# gadgiteration_v21.net
KiCad netlist of a schematic drawn in EAGLE
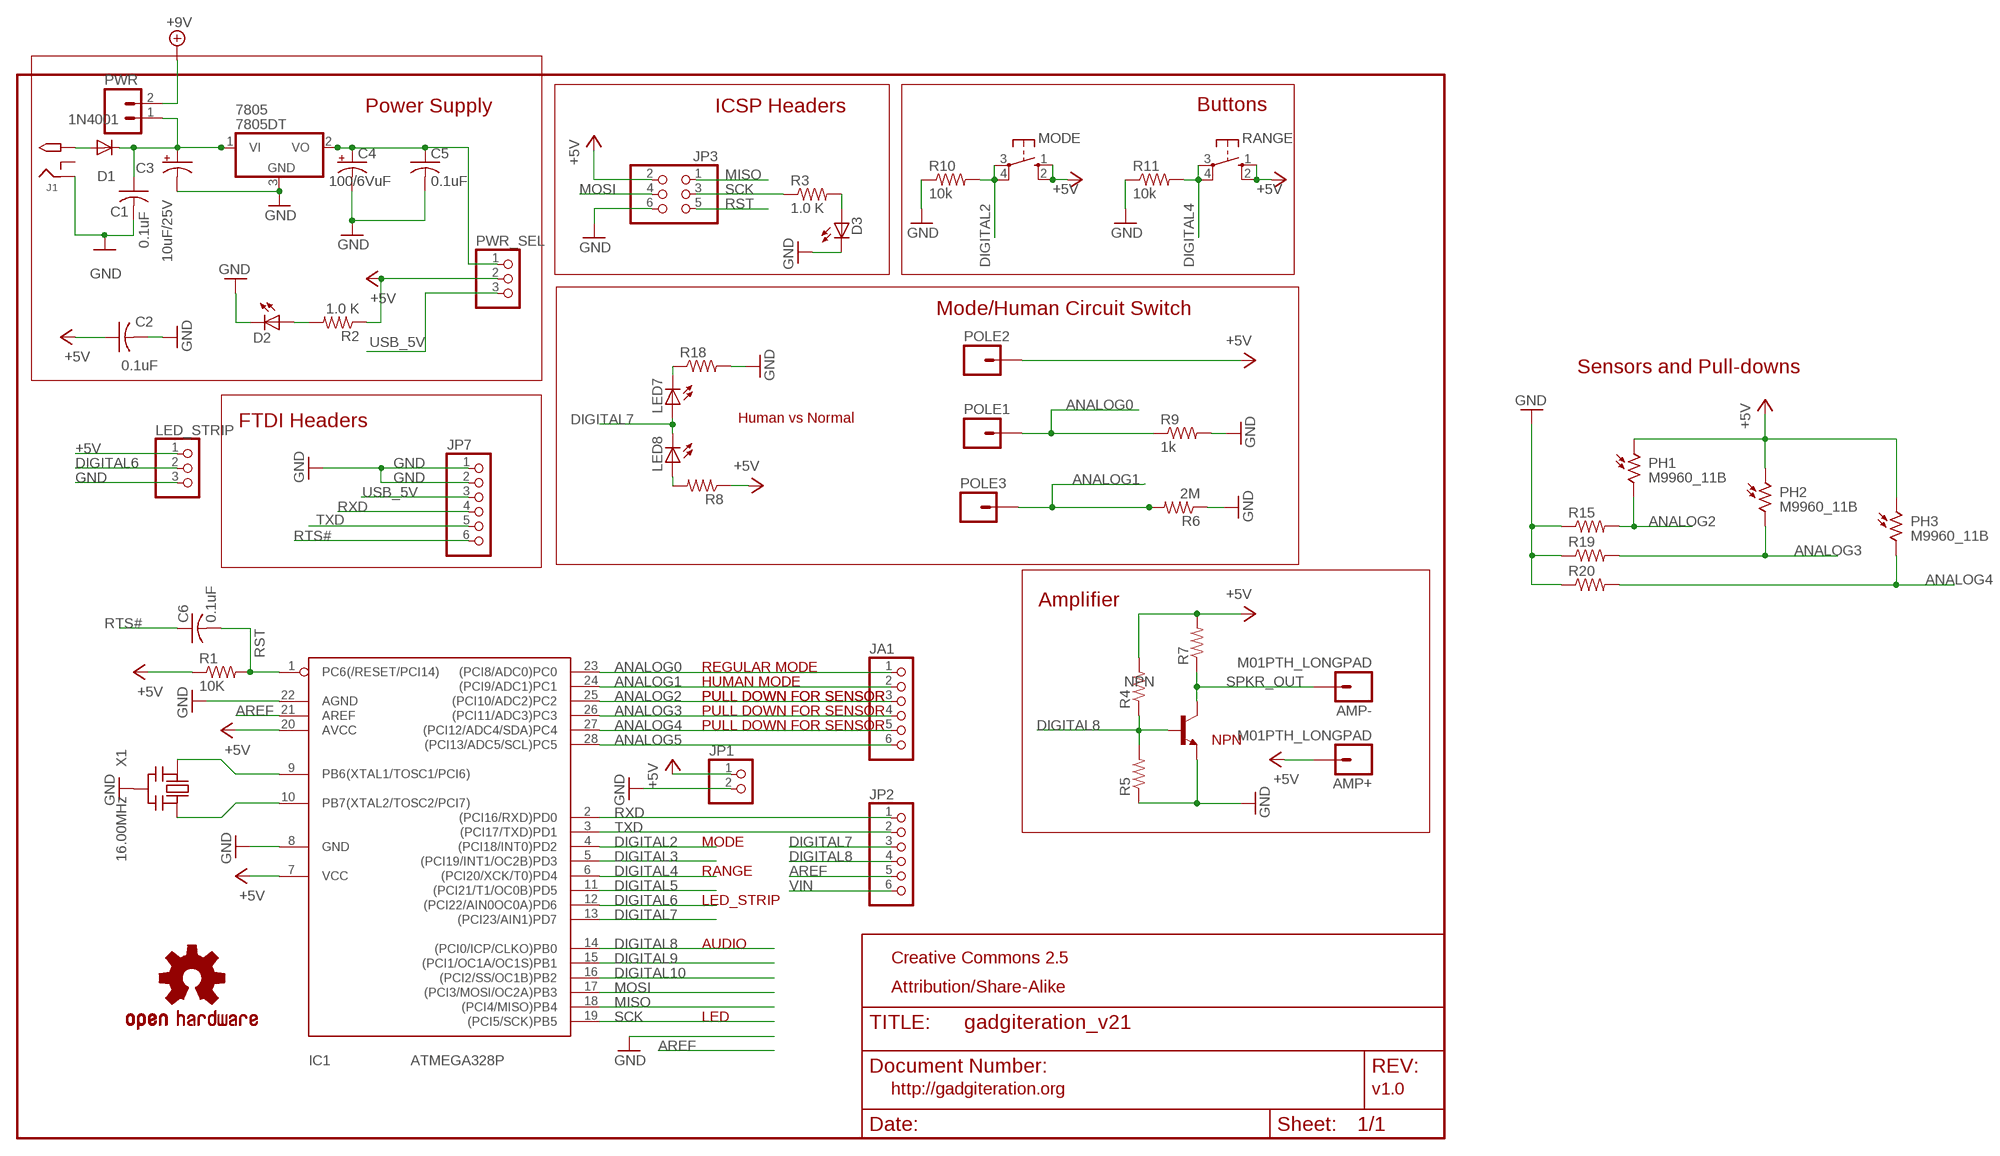
[diagram p0: schematic, sheet 1]

(export (version "E")
  (design (tool "Eeschema 10.0.6"))
  (components
    (comp (ref "7805")
      (value "7805DT")
      (footprint "eagle-import:TO252")
      (libsource (lib "eagle-import") (part "78DT05"))
    )
    (comp (ref "AMP+")
      (value "M01PTH_LONGPAD")
      (footprint "eagle-import:1X01_LONGPAD")
      (libsource (lib "eagle-import") (part "M01PTH_LONGPAD"))
    )
    (comp (ref "AMP-")
      (value "M01PTH_LONGPAD")
      (footprint "eagle-import:1X01_LONGPAD")
      (libsource (lib "eagle-import") (part "M01PTH_LONGPAD"))
    )
    (comp (ref "C1")
      (value "0.1uF")
      (footprint "eagle-import:C025-025X050")
      (libsource (lib "eagle-import") (part "C-US025-025X050"))
    )
    (comp (ref "C2")
      (value "0.1uF")
      (footprint "eagle-import:C025-025X050")
      (libsource (lib "eagle-import") (part "C-US025-025X050"))
    )
    (comp (ref "C3")
      (value "10uF/25V")
      (footprint "eagle-import:E2,5-6")
      (libsource (lib "eagle-import") (part "CPOL-USE2.5-6"))
    )
    (comp (ref "C4")
      (value "100/6VuF")
      (footprint "eagle-import:E2,5-6")
      (libsource (lib "eagle-import") (part "CPOL-USE2.5-6"))
    )
    (comp (ref "C5")
      (value "0.1uF")
      (footprint "eagle-import:C025-025X050")
      (libsource (lib "eagle-import") (part "C-US025-025X050"))
    )
    (comp (ref "C6")
      (value "0.1uF")
      (footprint "eagle-import:C025-025X050")
      (libsource (lib "eagle-import") (part "C-US025-025X050"))
    )
    (comp (ref "D1")
      (value "1N4001")
      (footprint "eagle-import:DIODE-1N4001")
      (libsource (lib "eagle-import") (part "DIODEPTH"))
    )
    (comp (ref "D2")
      (value "LED3MM")
      (footprint "eagle-import:LED3MM")
      (libsource (lib "eagle-import") (part "minimidi_LED3MM"))
    )
    (comp (ref "D3")
      (value "Green")
      (footprint "eagle-import:LED3MM")
      (libsource (lib "eagle-import") (part "minimidi_LED3MM"))
    )
    (comp (ref "IC1")
      (value "ATMEGA328P")
      (footprint "eagle-import:DIL28_3")
      (libsource (lib "eagle-import") (part "ATMEGA168PROUND"))
    )
    (comp (ref "J1")
      (value "2.1MMJACK")
      (footprint "eagle-import:PJ-102A")
      (libsource (lib "eagle-import") (part "2.1MMJACK"))
    )
    (comp (ref "JA1")
      (value "PINHD-1X6CB")
      (footprint "eagle-import:1X06-CLEANBIG")
      (libsource (lib "eagle-import") (part "carduino_PINHD-1X6CB"))
    )
    (comp (ref "JP1")
      (value "PINHD-1X2CB")
      (footprint "eagle-import:1X02-CB")
      (libsource (lib "eagle-import") (part "PINHD-1X2CB"))
    )
    (comp (ref "JP2")
      (value "PINHD-1X6CB")
      (footprint "eagle-import:1X06-CLEANBIG")
      (libsource (lib "eagle-import") (part "PINHD-1X6CB"))
    )
    (comp (ref "JP3")
      (value "PINHD-2X3")
      (footprint "eagle-import:2X03")
      (libsource (lib "eagle-import") (part "PINHD-2X3"))
    )
    (comp (ref "JP7")
      (value "PINHD-1X6CLEAN")
      (footprint "eagle-import:1X06-CLEAN")
      (libsource (lib "eagle-import") (part "carduino_PINHD-1X6CLEAN"))
    )
    (comp (ref "LED7")
      (value "LED3MM")
      (footprint "eagle-import:LED3MM")
      (libsource (lib "eagle-import") (part "LED3MM"))
    )
    (comp (ref "LED8")
      (value "LED3MM")
      (footprint "eagle-import:LED3MM")
      (libsource (lib "eagle-import") (part "LED3MM"))
    )
    (comp (ref "LED_STRIP")
      (value "PINHD-1X3")
      (footprint "eagle-import:1X03")
      (libsource (lib "eagle-import") (part "PINHD-1X3"))
    )
    (comp (ref "LOGO1")
      (value "OSHW-LOGOM")
      (footprint "eagle-import:OSHW-LOGO-M")
      (libsource (lib "eagle-import") (part "OSHW-LOGOM"))
    )
    (comp (ref "MODE")
      (value "10-XX")
      (footprint "eagle-import:B3F-10XX")
      (libsource (lib "eagle-import") (part "10-XX"))
    )
    (comp (ref "NPN")
      (value "-NPN-TO220V")
      (footprint "eagle-import:TO220V")
      (libsource (lib "eagle-import") (part "-NPN-TO220V"))
    )
    (comp (ref "PH1")
      (value "M9960_11B")
      (footprint "eagle-import:M9960")
      (libsource (lib "eagle-import") (part "M9960_11B"))
    )
    (comp (ref "PH2")
      (value "M9960_11B")
      (footprint "eagle-import:M9960")
      (libsource (lib "eagle-import") (part "M9960_11B"))
    )
    (comp (ref "PH3")
      (value "M9960_11B")
      (footprint "eagle-import:M9960")
      (libsource (lib "eagle-import") (part "M9960_11B"))
    )
    (comp (ref "POLE1")
      (value "M01PTH_LONGPAD")
      (footprint "eagle-import:1X01_LONGPAD")
      (libsource (lib "eagle-import") (part "M01PTH_LONGPAD"))
    )
    (comp (ref "POLE2")
      (value "M01PTH_LONGPAD")
      (footprint "eagle-import:1X01_LONGPAD")
      (libsource (lib "eagle-import") (part "M01PTH_LONGPAD"))
    )
    (comp (ref "POLE3")
      (value "M01PTH_LONGPAD")
      (footprint "eagle-import:1X01_LONGPAD")
      (libsource (lib "eagle-import") (part "M01PTH_LONGPAD"))
    )
    (comp (ref "PWR")
      (value "M02LOCK")
      (footprint "eagle-import:1X02_LOCK")
      (libsource (lib "eagle-import") (part "M02LOCK"))
    )
    (comp (ref "PWR_SEL")
      (value "PINHD-1X3")
      (footprint "eagle-import:1X03")
      (libsource (lib "eagle-import") (part "PINHD-1X3"))
    )
    (comp (ref "R1")
      (value "10K")
      (footprint "eagle-import:0204_5")
      (libsource (lib "eagle-import") (part "R-US_0204/5"))
    )
    (comp (ref "R2")
      (value "1.0 K")
      (footprint "eagle-import:0204_5")
      (libsource (lib "eagle-import") (part "R-US_0204/5"))
    )
    (comp (ref "R3")
      (value "1.0 K")
      (footprint "eagle-import:0204_5")
      (libsource (lib "eagle-import") (part "R-US_0204/5"))
    )
    (comp (ref "R4")
      (value "R-US_0204/5")
      (footprint "eagle-import:0204_5")
      (libsource (lib "eagle-import") (part "R-US_0204/5"))
    )
    (comp (ref "R5")
      (value "R-US_0204/5")
      (footprint "eagle-import:0204_5")
      (libsource (lib "eagle-import") (part "R-US_0204/5"))
    )
    (comp (ref "R6")
      (value "2M")
      (footprint "eagle-import:0204_5")
      (libsource (lib "eagle-import") (part "R-US_0204/5"))
    )
    (comp (ref "R7")
      (value "R-US_0204/5")
      (footprint "eagle-import:0204_5")
      (libsource (lib "eagle-import") (part "R-US_0204/5"))
    )
    (comp (ref "R8")
      (value "R-US_0204/5")
      (footprint "eagle-import:0204_5")
      (libsource (lib "eagle-import") (part "R-US_0204/5"))
    )
    (comp (ref "R9")
      (value "1k")
      (footprint "eagle-import:0204_5")
      (libsource (lib "eagle-import") (part "R-US_0204/5"))
    )
    (comp (ref "R10")
      (value "10k")
      (footprint "eagle-import:0204_5")
      (libsource (lib "eagle-import") (part "R-US_0204/5"))
    )
    (comp (ref "R11")
      (value "10k")
      (footprint "eagle-import:0204_5")
      (libsource (lib "eagle-import") (part "R-US_0204/5"))
    )
    (comp (ref "R15")
      (value "R-US_0204/5")
      (footprint "eagle-import:0204_5")
      (libsource (lib "eagle-import") (part "R-US_0204/5"))
    )
    (comp (ref "R18")
      (value "R-US_0204/5")
      (footprint "eagle-import:0204_5")
      (libsource (lib "eagle-import") (part "R-US_0204/5"))
    )
    (comp (ref "R19")
      (value "R-US_0204/5")
      (footprint "eagle-import:0204_5")
      (libsource (lib "eagle-import") (part "R-US_0204/5"))
    )
    (comp (ref "R20")
      (value "R-US_0204/5")
      (footprint "eagle-import:0204_5")
      (libsource (lib "eagle-import") (part "R-US_0204/5"))
    )
    (comp (ref "RANGE")
      (value "10-XX")
      (footprint "eagle-import:B3F-10XX")
      (libsource (lib "eagle-import") (part "10-XX"))
    )
    (comp (ref "X1")
      (value "16.00MHz")
      (footprint "eagle-import:CERM_OSC")
      (libsource (lib "eagle-import") (part "CERMOSCILL"))
    )
  )
  (nets
    (net (code "1") (name "+5V") (class "Default")
      (node (ref "AMP+") (pin "1") (pinfunction "1_1") (pintype "passive"))
      (node (ref "C2") (pin "1") (pinfunction "1_1") (pintype "passive"))
      (node (ref "IC1") (pin "20") (pinfunction "AVCC_20") (pintype "bidirectional"))
      (node (ref "IC1") (pin "7") (pinfunction "VCC_7") (pintype "bidirectional"))
      (node (ref "JP1") (pin "1") (pinfunction "1_1") (pintype "passive"))
      (node (ref "JP3") (pin "2") (pinfunction "2_2") (pintype "passive"))
      (node (ref "LED_STRIP") (pin "1") (pinfunction "1_1") (pintype "passive"))
      (node (ref "MODE") (pin "1") (pinfunction "S_1") (pintype "passive"))
      (node (ref "MODE") (pin "2") (pinfunction "S1_2") (pintype "passive"))
      (node (ref "PH1") (pin "1") (pinfunction "1_1") (pintype "passive"))
      (node (ref "PH2") (pin "1") (pinfunction "1_1") (pintype "passive"))
      (node (ref "PH3") (pin "1") (pinfunction "1_1") (pintype "passive"))
      (node (ref "POLE2") (pin "1") (pinfunction "1_1") (pintype "passive"))
      (node (ref "PWR_SEL") (pin "2") (pinfunction "2_2") (pintype "passive"))
      (node (ref "R1") (pin "1") (pinfunction "1_1") (pintype "passive"))
      (node (ref "R2") (pin "1") (pinfunction "1_1") (pintype "passive"))
      (node (ref "R4") (pin "2") (pinfunction "2_2") (pintype "passive"))
      (node (ref "R7") (pin "2") (pinfunction "2_2") (pintype "passive"))
      (node (ref "R8") (pin "1") (pinfunction "1_1") (pintype "passive"))
      (node (ref "RANGE") (pin "1") (pinfunction "S_1") (pintype "passive"))
      (node (ref "RANGE") (pin "2") (pinfunction "S1_2") (pintype "passive"))
    )
    (net (code "2") (name "+9V") (class "Default")
      (node (ref "PWR") (pin "2") (pinfunction "2_2") (pintype "passive"))
    )
    (net (code "3") (name "/ANALOG0") (class "Default")
      (node (ref "IC1") (pin "23") (pinfunction "(PCI8/ADC0)PC0_23") (pintype "bidirectional"))
      (node (ref "JA1") (pin "1") (pinfunction "1_1") (pintype "passive"))
      (node (ref "POLE1") (pin "1") (pinfunction "1_1") (pintype "passive"))
      (node (ref "R9") (pin "1") (pinfunction "1_1") (pintype "passive"))
    )
    (net (code "4") (name "/ANALOG1") (class "Default")
      (node (ref "IC1") (pin "24") (pinfunction "(PCI9/ADC1)PC1_24") (pintype "bidirectional"))
      (node (ref "JA1") (pin "2") (pinfunction "2_2") (pintype "passive"))
      (node (ref "POLE3") (pin "1") (pinfunction "1_1") (pintype "passive"))
      (node (ref "R6") (pin "2") (pinfunction "2_2") (pintype "passive"))
    )
    (net (code "5") (name "/ANALOG2") (class "Default")
      (node (ref "IC1") (pin "25") (pinfunction "(PCI10/ADC2)PC2_25") (pintype "bidirectional"))
      (node (ref "JA1") (pin "3") (pinfunction "3_3") (pintype "passive"))
      (node (ref "PH1") (pin "2") (pinfunction "2_2") (pintype "passive"))
      (node (ref "R15") (pin "2") (pinfunction "2_2") (pintype "passive"))
    )
    (net (code "6") (name "/ANALOG3") (class "Default")
      (node (ref "IC1") (pin "26") (pinfunction "(PCI11/ADC3)PC3_26") (pintype "bidirectional"))
      (node (ref "JA1") (pin "4") (pinfunction "4_4") (pintype "passive"))
      (node (ref "PH2") (pin "2") (pinfunction "2_2") (pintype "passive"))
      (node (ref "R19") (pin "2") (pinfunction "2_2") (pintype "passive"))
    )
    (net (code "7") (name "/ANALOG4") (class "Default")
      (node (ref "IC1") (pin "27") (pinfunction "(PCI12/ADC4/SDA)PC4_27") (pintype "bidirectional"))
      (node (ref "JA1") (pin "5") (pinfunction "5_5") (pintype "passive"))
      (node (ref "PH3") (pin "2") (pinfunction "2_2") (pintype "passive"))
      (node (ref "R20") (pin "2") (pinfunction "2_2") (pintype "passive"))
    )
    (net (code "8") (name "/ANALOG5") (class "Default")
      (node (ref "IC1") (pin "28") (pinfunction "(PCI13/ADC5/SCL)PC5_28") (pintype "bidirectional"))
      (node (ref "JA1") (pin "6") (pinfunction "6_6") (pintype "passive"))
    )
    (net (code "9") (name "/AREF") (class "Default")
      (node (ref "IC1") (pin "21") (pinfunction "AREF_21") (pintype "bidirectional"))
      (node (ref "JP2") (pin "5") (pinfunction "5_5") (pintype "passive"))
    )
    (net (code "10") (name "/DIGITAL2") (class "Default")
      (node (ref "IC1") (pin "4") (pinfunction "(PCI18/INT0)PD2_4") (pintype "bidirectional"))
      (node (ref "MODE") (pin "3") (pinfunction "P_3") (pintype "passive"))
      (node (ref "MODE") (pin "4") (pinfunction "P1_4") (pintype "passive"))
      (node (ref "R10") (pin "2") (pinfunction "2_2") (pintype "passive"))
    )
    (net (code "11") (name "/DIGITAL3") (class "Default")
      (node (ref "IC1") (pin "5") (pinfunction "(PCI19/INT1/OC2B)PD3_5") (pintype "bidirectional"))
    )
    (net (code "12") (name "/DIGITAL4") (class "Default")
      (node (ref "IC1") (pin "6") (pinfunction "(PCI20/XCK/T0)PD4_6") (pintype "bidirectional"))
      (node (ref "R11") (pin "2") (pinfunction "2_2") (pintype "passive"))
      (node (ref "RANGE") (pin "3") (pinfunction "P_3") (pintype "passive"))
      (node (ref "RANGE") (pin "4") (pinfunction "P1_4") (pintype "passive"))
    )
    (net (code "13") (name "/DIGITAL5") (class "Default")
      (node (ref "IC1") (pin "11") (pinfunction "(PCI21/T1/OC0B)PD5_11") (pintype "bidirectional"))
    )
    (net (code "14") (name "/DIGITAL6") (class "Default")
      (node (ref "IC1") (pin "12") (pinfunction "(PCI22/AIN0OC0A)PD6_12") (pintype "bidirectional"))
      (node (ref "LED_STRIP") (pin "2") (pinfunction "2_2") (pintype "passive"))
    )
    (net (code "15") (name "/DIGITAL7") (class "Default")
      (node (ref "IC1") (pin "13") (pinfunction "(PCI23/AIN1)PD7_13") (pintype "bidirectional"))
      (node (ref "JP2") (pin "3") (pinfunction "3_3") (pintype "passive"))
      (node (ref "LED7") (pin "A") (pinfunction "A_A") (pintype "passive"))
      (node (ref "LED8") (pin "K") (pinfunction "C_K") (pintype "passive"))
    )
    (net (code "16") (name "/DIGITAL8") (class "Default")
      (node (ref "IC1") (pin "14") (pinfunction "(PCI0/ICP/CLKO)PB0_14") (pintype "bidirectional"))
      (node (ref "JP2") (pin "4") (pinfunction "4_4") (pintype "passive"))
      (node (ref "NPN") (pin "1") (pinfunction "B_1") (pintype "passive"))
      (node (ref "R4") (pin "1") (pinfunction "1_1") (pintype "passive"))
      (node (ref "R5") (pin "2") (pinfunction "2_2") (pintype "passive"))
    )
    (net (code "17") (name "/DIGITAL9") (class "Default")
      (node (ref "IC1") (pin "15") (pinfunction "(PCI1/OC1A/OC1S)PB1_15") (pintype "bidirectional"))
    )
    (net (code "18") (name "/DIGITAL10") (class "Default")
      (node (ref "IC1") (pin "16") (pinfunction "(PCI2/SS/OC1B)PB2_16") (pintype "bidirectional"))
    )
    (net (code "19") (name "/MISO") (class "Default")
      (node (ref "IC1") (pin "18") (pinfunction "(PCI4/MISO)PB4_18") (pintype "bidirectional"))
      (node (ref "JP3") (pin "1") (pinfunction "1_1") (pintype "passive"))
    )
    (net (code "20") (name "/MOSI") (class "Default")
      (node (ref "IC1") (pin "17") (pinfunction "(PCI3/MOSI/OC2A)PB3_17") (pintype "bidirectional"))
      (node (ref "JP3") (pin "4") (pinfunction "4_4") (pintype "passive"))
    )
    (net (code "21") (name "/RST") (class "Default")
      (node (ref "C6") (pin "2") (pinfunction "2_2") (pintype "passive"))
      (node (ref "IC1") (pin "1") (pinfunction "PC6(/RESET/PCI14)_1") (pintype "bidirectional"))
      (node (ref "JP3") (pin "5") (pinfunction "5_5") (pintype "passive"))
      (node (ref "R1") (pin "2") (pinfunction "2_2") (pintype "passive"))
    )
    (net (code "22") (name "/RTS#") (class "Default")
      (node (ref "C6") (pin "1") (pinfunction "1_1") (pintype "passive"))
      (node (ref "JP7") (pin "6") (pinfunction "6_6") (pintype "passive"))
    )
    (net (code "23") (name "/RXD") (class "Default")
      (node (ref "IC1") (pin "2") (pinfunction "(PCI16/RXD)PD0_2") (pintype "bidirectional"))
      (node (ref "JP2") (pin "1") (pinfunction "1_1") (pintype "passive"))
      (node (ref "JP7") (pin "4") (pinfunction "4_4") (pintype "passive"))
    )
    (net (code "24") (name "/SCK") (class "Default")
      (node (ref "IC1") (pin "19") (pinfunction "(PCI5/SCK)PB5_19") (pintype "bidirectional"))
      (node (ref "JP3") (pin "3") (pinfunction "3_3") (pintype "passive"))
      (node (ref "R3") (pin "1") (pinfunction "1_1") (pintype "passive"))
    )
    (net (code "25") (name "/SPKR_OUT") (class "Default")
      (node (ref "AMP-") (pin "1") (pinfunction "1_1") (pintype "passive"))
      (node (ref "NPN") (pin "2") (pinfunction "C_2") (pintype "passive"))
      (node (ref "R7") (pin "1") (pinfunction "1_1") (pintype "passive"))
    )
    (net (code "26") (name "/TXD") (class "Default")
      (node (ref "IC1") (pin "3") (pinfunction "(PCI17/TXD)PD1_3") (pintype "bidirectional"))
      (node (ref "JP2") (pin "2") (pinfunction "2_2") (pintype "passive"))
      (node (ref "JP7") (pin "5") (pinfunction "5_5") (pintype "passive"))
    )
    (net (code "27") (name "/USB_5V") (class "Default")
      (node (ref "JP7") (pin "3") (pinfunction "3_3") (pintype "passive"))
      (node (ref "PWR_SEL") (pin "3") (pinfunction "3_3") (pintype "passive"))
    )
    (net (code "28") (name "/VIN") (class "Default")
      (node (ref "7805") (pin "1") (pinfunction "VI_1") (pintype "input"))
      (node (ref "C1") (pin "1") (pinfunction "1_1") (pintype "passive"))
      (node (ref "C3") (pin "+") (pinfunction "+_+") (pintype "passive"))
      (node (ref "D1") (pin "C") (pinfunction "C_C") (pintype "passive"))
      (node (ref "JP2") (pin "6") (pinfunction "6_6") (pintype "passive"))
      (node (ref "PWR") (pin "1") (pinfunction "1_1") (pintype "passive"))
    )
    (net (code "29") (name "GND") (class "Default")
      (node (ref "7805") (pin "3") (pinfunction "GND_3") (pintype "passive"))
      (node (ref "C1") (pin "2") (pinfunction "2_2") (pintype "passive"))
      (node (ref "C2") (pin "2") (pinfunction "2_2") (pintype "passive"))
      (node (ref "C3") (pin "-") (pinfunction "-_-") (pintype "passive"))
      (node (ref "C4") (pin "-") (pinfunction "-_-") (pintype "passive"))
      (node (ref "C5") (pin "2") (pinfunction "2_2") (pintype "passive"))
      (node (ref "D2") (pin "K") (pinfunction "C_K") (pintype "passive"))
      (node (ref "D3") (pin "K") (pinfunction "C_K") (pintype "passive"))
      (node (ref "IC1") (pin "22") (pinfunction "AGND_22") (pintype "bidirectional"))
      (node (ref "IC1") (pin "8") (pinfunction "GND_8") (pintype "bidirectional"))
      (node (ref "J1") (pin "RING") (pinfunction "RING_RING") (pintype "bidirectional"))
      (node (ref "JP1") (pin "2") (pinfunction "2_2") (pintype "passive"))
      (node (ref "JP3") (pin "6") (pinfunction "6_6") (pintype "passive"))
      (node (ref "JP7") (pin "1") (pinfunction "1_1") (pintype "passive"))
      (node (ref "JP7") (pin "2") (pinfunction "2_2") (pintype "passive"))
      (node (ref "LED_STRIP") (pin "3") (pinfunction "3_3") (pintype "passive"))
      (node (ref "NPN") (pin "3") (pinfunction "E_3") (pintype "passive"))
      (node (ref "R10") (pin "1") (pinfunction "1_1") (pintype "passive"))
      (node (ref "R11") (pin "1") (pinfunction "1_1") (pintype "passive"))
      (node (ref "R15") (pin "1") (pinfunction "1_1") (pintype "passive"))
      (node (ref "R18") (pin "2") (pinfunction "2_2") (pintype "passive"))
      (node (ref "R19") (pin "1") (pinfunction "1_1") (pintype "passive"))
      (node (ref "R20") (pin "1") (pinfunction "1_1") (pintype "passive"))
      (node (ref "R5") (pin "1") (pinfunction "1_1") (pintype "passive"))
      (node (ref "R6") (pin "1") (pinfunction "1_1") (pintype "passive"))
      (node (ref "R9") (pin "2") (pinfunction "2_2") (pintype "passive"))
      (node (ref "X1") (pin "P$2") (pinfunction "GND_P$2") (pintype "bidirectional"))
    )
    (net (code "30") (name "Net-(7805-VO)") (class "Default")
      (node (ref "7805") (pin "2") (pinfunction "VO_2") (pintype "passive"))
      (node (ref "C4") (pin "+") (pinfunction "+_+") (pintype "passive"))
      (node (ref "C5") (pin "1") (pinfunction "1_1") (pintype "passive"))
      (node (ref "PWR_SEL") (pin "1") (pinfunction "1_1") (pintype "passive"))
    )
    (net (code "31") (name "Net-(D1-PadA)") (class "Default")
      (node (ref "D1") (pin "A") (pinfunction "A_A") (pintype "passive"))
      (node (ref "J1") (pin "TIP") (pinfunction "TIP_TIP") (pintype "bidirectional"))
    )
    (net (code "32") (name "Net-(D2-PadA)") (class "Default")
      (node (ref "D2") (pin "A") (pinfunction "A_A") (pintype "passive"))
      (node (ref "R2") (pin "2") (pinfunction "2_2") (pintype "passive"))
    )
    (net (code "33") (name "Net-(D3-PadA)") (class "Default")
      (node (ref "D3") (pin "A") (pinfunction "A_A") (pintype "passive"))
      (node (ref "R3") (pin "2") (pinfunction "2_2") (pintype "passive"))
    )
    (net (code "34") (name "Net-(IC1-PB6(XTAL1{slash}TOSC1{slash}PCI6))") (class "Default")
      (node (ref "IC1") (pin "9") (pinfunction "PB6(XTAL1/TOSC1/PCI6)_9") (pintype "bidirectional"))
      (node (ref "X1") (pin "P$1") (pinfunction "IN_P$1") (pintype "bidirectional"))
    )
    (net (code "35") (name "Net-(IC1-PB7(XTAL2{slash}TOSC2{slash}PCI7))") (class "Default")
      (node (ref "IC1") (pin "10") (pinfunction "PB7(XTAL2/TOSC2/PCI7)_10") (pintype "bidirectional"))
      (node (ref "X1") (pin "P$3") (pinfunction "OUT_P$3") (pintype "bidirectional"))
    )
    (net (code "36") (name "Net-(LED7-C)") (class "Default")
      (node (ref "LED7") (pin "K") (pinfunction "C_K") (pintype "passive"))
      (node (ref "R18") (pin "1") (pinfunction "1_1") (pintype "passive"))
    )
    (net (code "37") (name "Net-(LED8-PadA)") (class "Default")
      (node (ref "LED8") (pin "A") (pinfunction "A_A") (pintype "passive"))
      (node (ref "R8") (pin "2") (pinfunction "2_2") (pintype "passive"))
    )
    (net (code "38") (name "unconnected-(J1-PadRING_SW)") (class "Default")
      (node (ref "J1") (pin "RING_SW") (pinfunction "RING_SW_RING_SW") (pintype "bidirectional"))
    )
  )
)
